# Sensors.net
KiCad netlist of a schematic drawn in Altium Designer
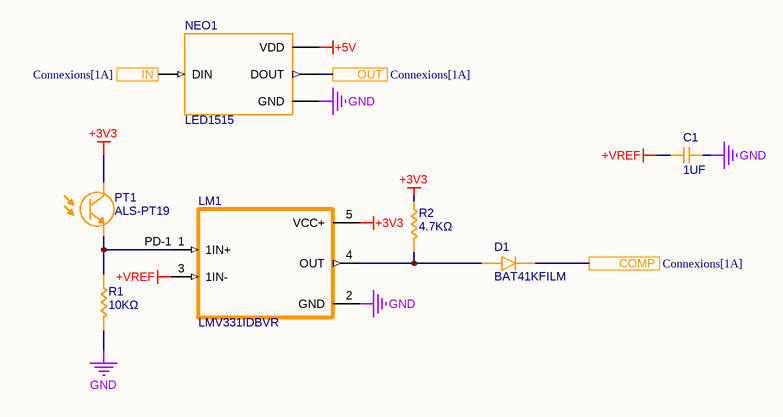
[diagram p0: Sensors.SchDoc]

(export (version "E")
  (design (tool "Eeschema 10.0.6"))
  (components
    (comp (ref "C1")
      (value "1UF")
      (footprint "CAP_0603")
      (description "Capacitor SMD 0603 generic")
      (libsource (lib "RC") (part "CAP_0603"))
    )
    (comp (ref "D1") (value "BAT41KFILM") (footprint "BAT41KFILM") (libsource (lib "RC") (part "BAT41KFILM")))
    (comp (ref "LM1")
      (value "LMV331IDBVR")
      (footprint "LMV331IDBVR")
      (libsource (lib "GenericRC") (part "LMV331IDBVR"))
    )
    (comp (ref "NEO1") (value "LED1515") (footprint "LED1515") (libsource (lib "RC") (part "LED1515")))
    (comp (ref "PT1") (value "ALS-PT19") (footprint "ALS-PT19") (libsource (lib "RC") (part "ALS-PT19")))
    (comp (ref "R1")
      (value "10KΩ")
      (footprint "RES_0603")
      (description "Resistor SMD 0603 generic")
      (libsource (lib "GenericRC") (part "RES_0603"))
    )
    (comp (ref "R2")
      (value "4.7KΩ")
      (footprint "RES_0603")
      (description "Resistor SMD 0603 generic")
      (libsource (lib "GenericRC") (part "RES_0603"))
    )
  )
  (nets
    (net (code "1") (name "+3V3") (class "Default")
      (node (ref "LM1") (pin "5") (pinfunction "VCC+_5") (pintype "power_in"))
      (node (ref "PT1") (pin "C") (pinfunction "C_C") (pintype "passive"))
      (node (ref "R2") (pin "2") (pintype "passive"))
    )
    (net (code "2") (name "+5V") (class "Default")
      (node (ref "NEO1") (pin "VDD") (pinfunction "VDD_VDD") (pintype "power_in"))
    )
    (net (code "3") (name "+VREF") (class "Default")
      (node (ref "C1") (pin "2") (pintype "passive"))
      (node (ref "LM1") (pin "3") (pinfunction "1IN-_3") (pintype "input"))
    )
    (net (code "4") (name "/COMP") (class "Default")
      (node (ref "D1") (pin "C") (pinfunction "K_C") (pintype "passive"))
    )
    (net (code "5") (name "/IN") (class "Default")
      (node (ref "NEO1") (pin "DIN") (pinfunction "DIN_DIN") (pintype "input"))
    )
    (net (code "6") (name "/OUT") (class "Default")
      (node (ref "NEO1") (pin "DOUT") (pinfunction "DOUT_DOUT") (pintype "output"))
    )
    (net (code "7") (name "/PD-1") (class "Default")
      (node (ref "LM1") (pin "1") (pinfunction "1IN+_1") (pintype "input"))
      (node (ref "PT1") (pin "E") (pinfunction "E_E") (pintype "passive"))
      (node (ref "R1") (pin "2") (pintype "passive"))
    )
    (net (code "8") (name "GND") (class "Default")
      (node (ref "C1") (pin "1") (pintype "passive"))
      (node (ref "LM1") (pin "2") (pinfunction "GND_2") (pintype "power_in"))
      (node (ref "NEO1") (pin "GND") (pinfunction "GND_GND") (pintype "power_in"))
      (node (ref "R1") (pin "1") (pintype "passive"))
    )
    (net (code "9") (name "Net-(LM1-OUT)") (class "Default")
      (node (ref "D1") (pin "A") (pinfunction "A_A") (pintype "passive"))
      (node (ref "LM1") (pin "4") (pinfunction "OUT_4") (pintype "output"))
      (node (ref "R2") (pin "1") (pintype "passive"))
    )
  )
)
